# VIDEO.net
KiCad netlist of a schematic drawn in Altium Designer
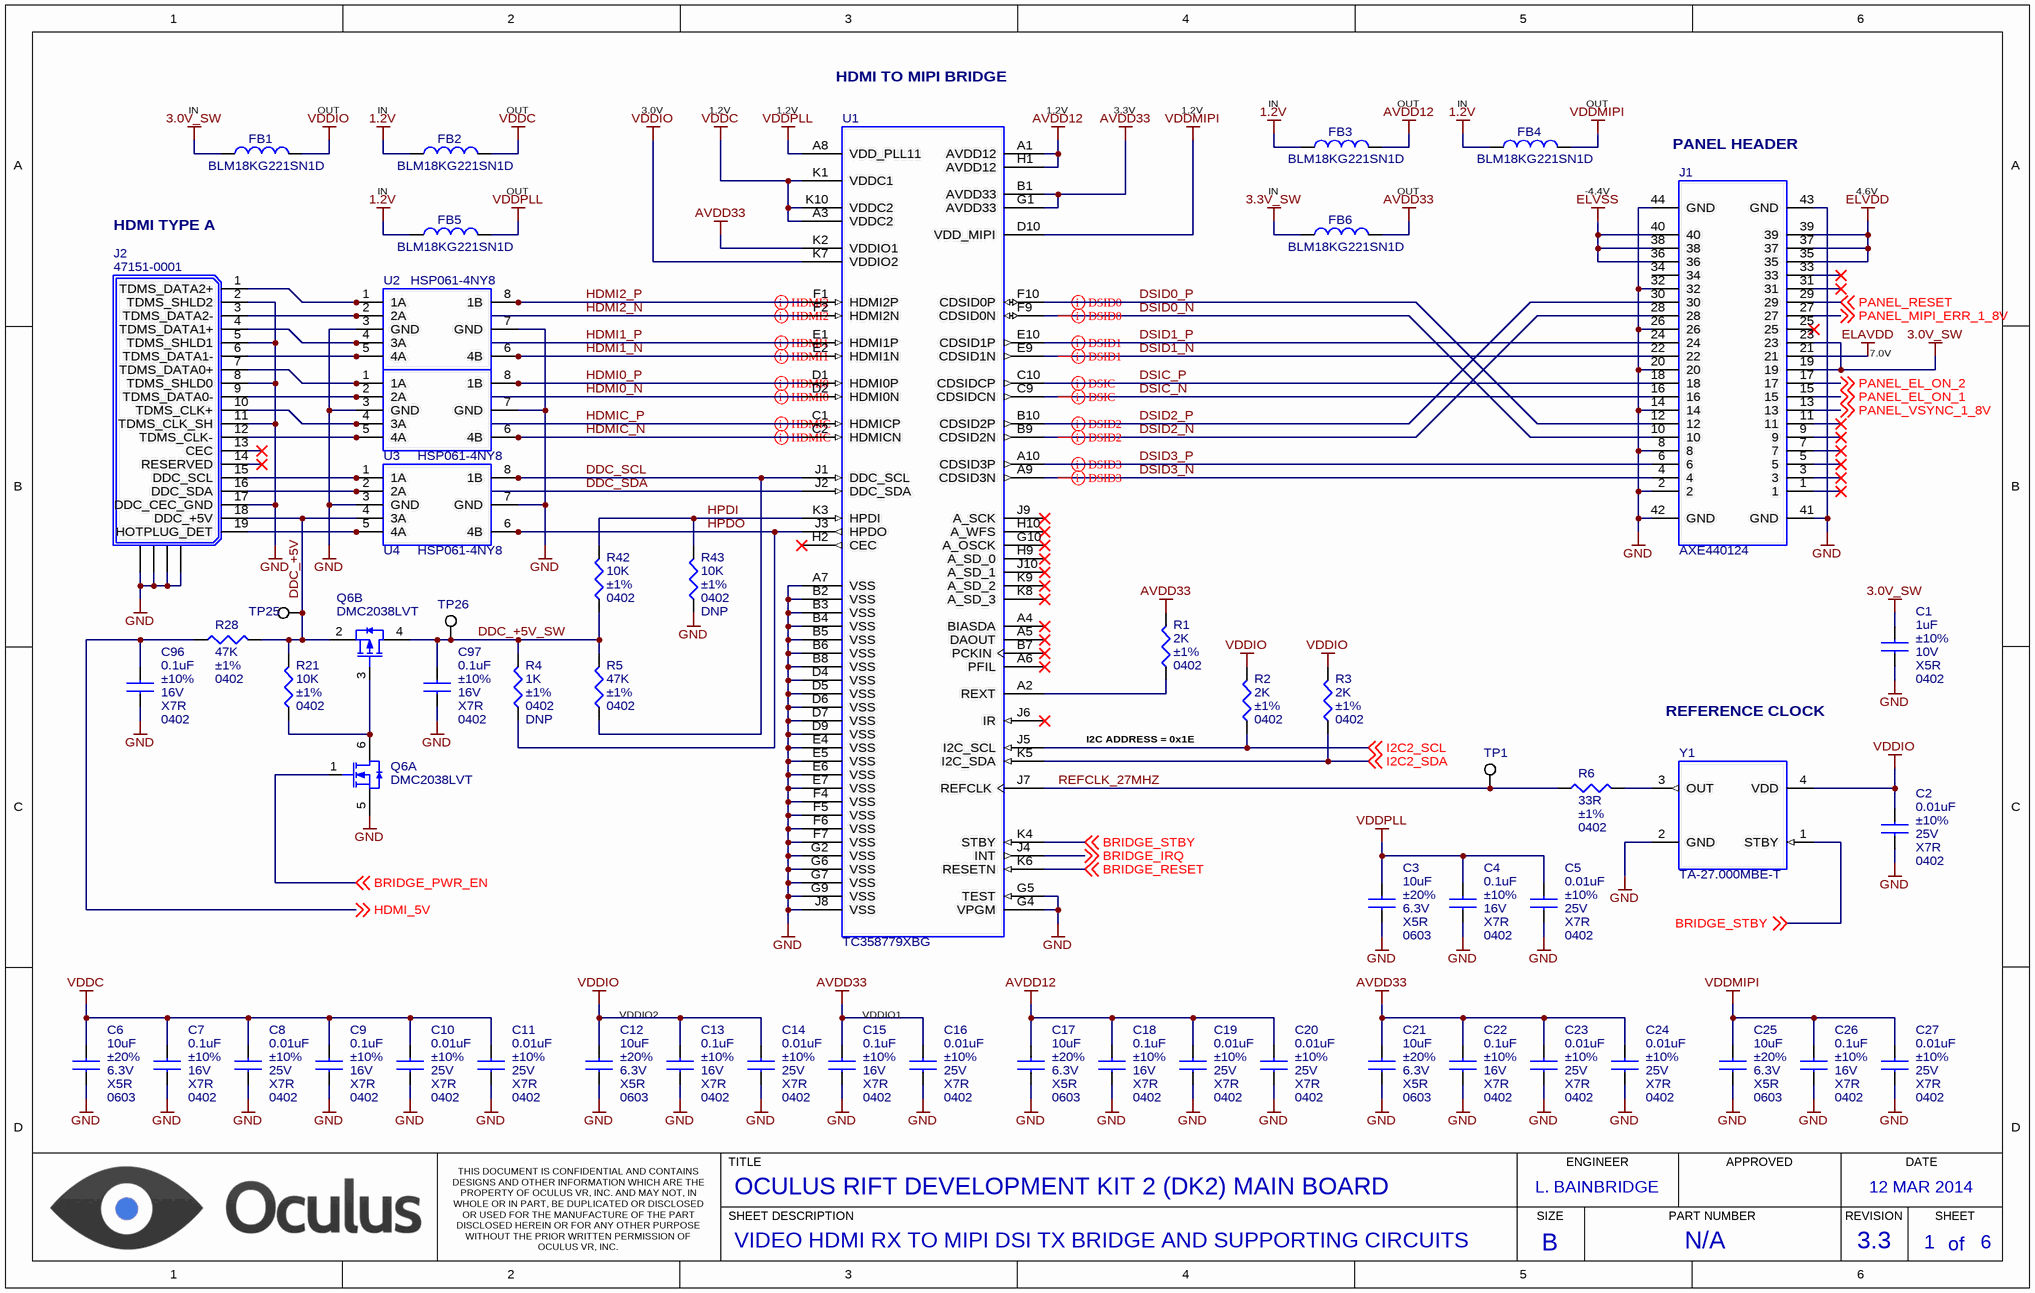
[diagram p0: VIDEO.SchDoc]

(export (version "E")
  (design (tool "Eeschema 10.0.6"))
  (components
    (comp (ref "C1")
      (value "1uF")
      (footprint "CAP_CERAMIC_0402")
      (description "CAP, CERAMIC, 1uF, ±10%, 10V, X5R, 0402")
      (fields
        (field (name "MANUFACTURER") "MURATA ELECTRONICS")
        (field (name "PART NUMBER") "GRM155R61A105KE15D")
        (field (name "TOLERANCE") "±10%")
        (field (name "VOLTAGE") "10V")
        (field (name "DIELECTRIC") "X5R")
        (field (name "PACKAGE") "0402")
      )
      (libsource (lib "DK2") (part "CAP, CERAMIC"))
    )
    (comp (ref "C2")
      (value "0.01uF")
      (footprint "CAP_CERAMIC_0402")
      (description "CAP, CERAMIC, 0.01uF, ±10%, 25V, X7R, 0402")
      (fields
        (field (name "MANUFACTURER") "MURATA ELECTRONICS")
        (field (name "PART NUMBER") "GRM155R71E103KA01D")
        (field (name "TOLERANCE") "±10%")
        (field (name "VOLTAGE") "25V")
        (field (name "DIELECTRIC") "X7R")
        (field (name "PACKAGE") "0402")
      )
      (libsource (lib "DK2") (part "CAP, CERAMIC"))
    )
    (comp (ref "C3")
      (value "10uF")
      (footprint "CAP_CERAMIC_0603")
      (description "CAP, CERAMIC, 10uF, ±20%, 6.3V, X5R, 0603")
      (fields
        (field (name "MANUFACTURER") "MURATA ELECTRONICS")
        (field (name "PART NUMBER") "GRM188R60J106ME47D")
        (field (name "TOLERANCE") "±20%")
        (field (name "VOLTAGE") "6.3V")
        (field (name "DIELECTRIC") "X5R")
        (field (name "PACKAGE") "0603")
      )
      (libsource (lib "DK2") (part "CAP, CERAMIC"))
    )
    (comp (ref "C4")
      (value "0.1uF")
      (footprint "CAP_CERAMIC_0402")
      (description "CAP, CERAMIC, 0.1uF, ±10%, 16V, X7R, 0402")
      (fields
        (field (name "MANUFACTURER") "MURATA ELECTRONICS")
        (field (name "PART NUMBER") "GRM155R71C104KA88D")
        (field (name "TOLERANCE") "±10%")
        (field (name "VOLTAGE") "16V")
        (field (name "DIELECTRIC") "X7R")
        (field (name "PACKAGE") "0402")
      )
      (libsource (lib "DK2") (part "CAP, CERAMIC"))
    )
    (comp (ref "C5")
      (value "0.01uF")
      (footprint "CAP_CERAMIC_0402")
      (description "CAP, CERAMIC, 0.01uF, ±10%, 25V, X7R, 0402")
      (fields
        (field (name "MANUFACTURER") "MURATA ELECTRONICS")
        (field (name "PART NUMBER") "GRM155R71E103KA01D")
        (field (name "TOLERANCE") "±10%")
        (field (name "VOLTAGE") "25V")
        (field (name "DIELECTRIC") "X7R")
        (field (name "PACKAGE") "0402")
      )
      (libsource (lib "DK2") (part "CAP, CERAMIC"))
    )
    (comp (ref "C6")
      (value "10uF")
      (footprint "CAP_CERAMIC_0603")
      (description "CAP, CERAMIC, 10uF, ±20%, 6.3V, X5R, 0603")
      (fields
        (field (name "MANUFACTURER") "MURATA ELECTRONICS")
        (field (name "PART NUMBER") "GRM188R60J106ME47D")
        (field (name "TOLERANCE") "±20%")
        (field (name "VOLTAGE") "6.3V")
        (field (name "DIELECTRIC") "X5R")
        (field (name "PACKAGE") "0603")
      )
      (libsource (lib "DK2") (part "CAP, CERAMIC"))
    )
    (comp (ref "C7")
      (value "0.1uF")
      (footprint "CAP_CERAMIC_0402")
      (description "CAP, CERAMIC, 0.1uF, ±10%, 16V, X7R, 0402")
      (fields
        (field (name "MANUFACTURER") "MURATA ELECTRONICS")
        (field (name "PART NUMBER") "GRM155R71C104KA88D")
        (field (name "TOLERANCE") "±10%")
        (field (name "VOLTAGE") "16V")
        (field (name "DIELECTRIC") "X7R")
        (field (name "PACKAGE") "0402")
      )
      (libsource (lib "DK2") (part "CAP, CERAMIC"))
    )
    (comp (ref "C8")
      (value "0.01uF")
      (footprint "CAP_CERAMIC_0402")
      (description "CAP, CERAMIC, 0.01uF, ±10%, 25V, X7R, 0402")
      (fields
        (field (name "MANUFACTURER") "MURATA ELECTRONICS")
        (field (name "PART NUMBER") "GRM155R71E103KA01D")
        (field (name "TOLERANCE") "±10%")
        (field (name "VOLTAGE") "25V")
        (field (name "DIELECTRIC") "X7R")
        (field (name "PACKAGE") "0402")
      )
      (libsource (lib "DK2") (part "CAP, CERAMIC"))
    )
    (comp (ref "C9")
      (value "0.1uF")
      (footprint "CAP_CERAMIC_0402")
      (description "CAP, CERAMIC, 0.1uF, ±10%, 16V, X7R, 0402")
      (fields
        (field (name "MANUFACTURER") "MURATA ELECTRONICS")
        (field (name "PART NUMBER") "GRM155R71C104KA88D")
        (field (name "TOLERANCE") "±10%")
        (field (name "VOLTAGE") "16V")
        (field (name "DIELECTRIC") "X7R")
        (field (name "PACKAGE") "0402")
      )
      (libsource (lib "DK2") (part "CAP, CERAMIC"))
    )
    (comp (ref "C10")
      (value "0.01uF")
      (footprint "CAP_CERAMIC_0402")
      (description "CAP, CERAMIC, 0.01uF, ±10%, 25V, X7R, 0402")
      (fields
        (field (name "MANUFACTURER") "MURATA ELECTRONICS")
        (field (name "PART NUMBER") "GRM155R71E103KA01D")
        (field (name "TOLERANCE") "±10%")
        (field (name "VOLTAGE") "25V")
        (field (name "DIELECTRIC") "X7R")
        (field (name "PACKAGE") "0402")
      )
      (libsource (lib "DK2") (part "CAP, CERAMIC"))
    )
    (comp (ref "C11")
      (value "0.01uF")
      (footprint "CAP_CERAMIC_0402")
      (description "CAP, CERAMIC, 0.01uF, ±10%, 25V, X7R, 0402")
      (fields
        (field (name "MANUFACTURER") "MURATA ELECTRONICS")
        (field (name "PART NUMBER") "GRM155R71E103KA01D")
        (field (name "TOLERANCE") "±10%")
        (field (name "VOLTAGE") "25V")
        (field (name "DIELECTRIC") "X7R")
        (field (name "PACKAGE") "0402")
      )
      (libsource (lib "DK2") (part "CAP, CERAMIC"))
    )
    (comp (ref "C12")
      (value "10uF")
      (footprint "CAP_CERAMIC_0603")
      (description "CAP, CERAMIC, 10uF, ±20%, 6.3V, X5R, 0603")
      (fields
        (field (name "MANUFACTURER") "MURATA ELECTRONICS")
        (field (name "PART NUMBER") "GRM188R60J106ME47D")
        (field (name "TOLERANCE") "±20%")
        (field (name "VOLTAGE") "6.3V")
        (field (name "DIELECTRIC") "X5R")
        (field (name "PACKAGE") "0603")
      )
      (libsource (lib "DK2") (part "CAP, CERAMIC"))
    )
    (comp (ref "C13")
      (value "0.1uF")
      (footprint "CAP_CERAMIC_0402")
      (description "CAP, CERAMIC, 0.1uF, ±10%, 16V, X7R, 0402")
      (fields
        (field (name "MANUFACTURER") "MURATA ELECTRONICS")
        (field (name "PART NUMBER") "GRM155R71C104KA88D")
        (field (name "TOLERANCE") "±10%")
        (field (name "VOLTAGE") "16V")
        (field (name "DIELECTRIC") "X7R")
        (field (name "PACKAGE") "0402")
      )
      (libsource (lib "DK2") (part "CAP, CERAMIC"))
    )
    (comp (ref "C14")
      (value "0.01uF")
      (footprint "CAP_CERAMIC_0402")
      (description "CAP, CERAMIC, 0.01uF, ±10%, 25V, X7R, 0402")
      (fields
        (field (name "MANUFACTURER") "MURATA ELECTRONICS")
        (field (name "PART NUMBER") "GRM155R71E103KA01D")
        (field (name "TOLERANCE") "±10%")
        (field (name "VOLTAGE") "25V")
        (field (name "DIELECTRIC") "X7R")
        (field (name "PACKAGE") "0402")
      )
      (libsource (lib "DK2") (part "CAP, CERAMIC"))
    )
    (comp (ref "C15")
      (value "0.1uF")
      (footprint "CAP_CERAMIC_0402")
      (description "CAP, CERAMIC, 0.1uF, ±10%, 16V, X7R, 0402")
      (fields
        (field (name "MANUFACTURER") "MURATA ELECTRONICS")
        (field (name "PART NUMBER") "GRM155R71C104KA88D")
        (field (name "TOLERANCE") "±10%")
        (field (name "VOLTAGE") "16V")
        (field (name "DIELECTRIC") "X7R")
        (field (name "PACKAGE") "0402")
      )
      (libsource (lib "DK2") (part "CAP, CERAMIC"))
    )
    (comp (ref "C16")
      (value "0.01uF")
      (footprint "CAP_CERAMIC_0402")
      (description "CAP, CERAMIC, 0.01uF, ±10%, 25V, X7R, 0402")
      (fields
        (field (name "MANUFACTURER") "MURATA ELECTRONICS")
        (field (name "PART NUMBER") "GRM155R71E103KA01D")
        (field (name "TOLERANCE") "±10%")
        (field (name "VOLTAGE") "25V")
        (field (name "DIELECTRIC") "X7R")
        (field (name "PACKAGE") "0402")
      )
      (libsource (lib "DK2") (part "CAP, CERAMIC"))
    )
    (comp (ref "C17")
      (value "10uF")
      (footprint "CAP_CERAMIC_0603")
      (description "CAP, CERAMIC, 10uF, ±20%, 6.3V, X5R, 0603")
      (fields
        (field (name "MANUFACTURER") "MURATA ELECTRONICS")
        (field (name "PART NUMBER") "GRM188R60J106ME47D")
        (field (name "TOLERANCE") "±20%")
        (field (name "VOLTAGE") "6.3V")
        (field (name "DIELECTRIC") "X5R")
        (field (name "PACKAGE") "0603")
      )
      (libsource (lib "DK2") (part "CAP, CERAMIC"))
    )
    (comp (ref "C18")
      (value "0.1uF")
      (footprint "CAP_CERAMIC_0402")
      (description "CAP, CERAMIC, 0.1uF, ±10%, 16V, X7R, 0402")
      (fields
        (field (name "MANUFACTURER") "MURATA ELECTRONICS")
        (field (name "PART NUMBER") "GRM155R71C104KA88D")
        (field (name "TOLERANCE") "±10%")
        (field (name "VOLTAGE") "16V")
        (field (name "DIELECTRIC") "X7R")
        (field (name "PACKAGE") "0402")
      )
      (libsource (lib "DK2") (part "CAP, CERAMIC"))
    )
    (comp (ref "C19")
      (value "0.01uF")
      (footprint "CAP_CERAMIC_0402")
      (description "CAP, CERAMIC, 0.01uF, ±10%, 25V, X7R, 0402")
      (fields
        (field (name "MANUFACTURER") "MURATA ELECTRONICS")
        (field (name "PART NUMBER") "GRM155R71E103KA01D")
        (field (name "TOLERANCE") "±10%")
        (field (name "VOLTAGE") "25V")
        (field (name "DIELECTRIC") "X7R")
        (field (name "PACKAGE") "0402")
      )
      (libsource (lib "DK2") (part "CAP, CERAMIC"))
    )
    (comp (ref "C20")
      (value "0.01uF")
      (footprint "CAP_CERAMIC_0402")
      (description "CAP, CERAMIC, 0.01uF, ±10%, 25V, X7R, 0402")
      (fields
        (field (name "MANUFACTURER") "MURATA ELECTRONICS")
        (field (name "PART NUMBER") "GRM155R71E103KA01D")
        (field (name "TOLERANCE") "±10%")
        (field (name "VOLTAGE") "25V")
        (field (name "DIELECTRIC") "X7R")
        (field (name "PACKAGE") "0402")
      )
      (libsource (lib "DK2") (part "CAP, CERAMIC"))
    )
    (comp (ref "C21")
      (value "10uF")
      (footprint "CAP_CERAMIC_0603")
      (description "CAP, CERAMIC, 10uF, ±20%, 6.3V, X5R, 0603")
      (fields
        (field (name "MANUFACTURER") "MURATA ELECTRONICS")
        (field (name "PART NUMBER") "GRM188R60J106ME47D")
        (field (name "TOLERANCE") "±20%")
        (field (name "VOLTAGE") "6.3V")
        (field (name "DIELECTRIC") "X5R")
        (field (name "PACKAGE") "0603")
      )
      (libsource (lib "DK2") (part "CAP, CERAMIC"))
    )
    (comp (ref "C22")
      (value "0.1uF")
      (footprint "CAP_CERAMIC_0402")
      (description "CAP, CERAMIC, 0.1uF, ±10%, 16V, X7R, 0402")
      (fields
        (field (name "MANUFACTURER") "MURATA ELECTRONICS")
        (field (name "PART NUMBER") "GRM155R71C104KA88D")
        (field (name "TOLERANCE") "±10%")
        (field (name "VOLTAGE") "16V")
        (field (name "DIELECTRIC") "X7R")
        (field (name "PACKAGE") "0402")
      )
      (libsource (lib "DK2") (part "CAP, CERAMIC"))
    )
    (comp (ref "C23")
      (value "0.01uF")
      (footprint "CAP_CERAMIC_0402")
      (description "CAP, CERAMIC, 0.01uF, ±10%, 25V, X7R, 0402")
      (fields
        (field (name "MANUFACTURER") "MURATA ELECTRONICS")
        (field (name "PART NUMBER") "GRM155R71E103KA01D")
        (field (name "TOLERANCE") "±10%")
        (field (name "VOLTAGE") "25V")
        (field (name "DIELECTRIC") "X7R")
        (field (name "PACKAGE") "0402")
      )
      (libsource (lib "DK2") (part "CAP, CERAMIC"))
    )
    (comp (ref "C24")
      (value "0.01uF")
      (footprint "CAP_CERAMIC_0402")
      (description "CAP, CERAMIC, 0.01uF, ±10%, 25V, X7R, 0402")
      (fields
        (field (name "MANUFACTURER") "MURATA ELECTRONICS")
        (field (name "PART NUMBER") "GRM155R71E103KA01D")
        (field (name "TOLERANCE") "±10%")
        (field (name "VOLTAGE") "25V")
        (field (name "DIELECTRIC") "X7R")
        (field (name "PACKAGE") "0402")
      )
      (libsource (lib "DK2") (part "CAP, CERAMIC"))
    )
    (comp (ref "C25")
      (value "10uF")
      (footprint "CAP_CERAMIC_0603")
      (description "CAP, CERAMIC, 10uF, ±20%, 6.3V, X5R, 0603")
      (fields
        (field (name "MANUFACTURER") "MURATA ELECTRONICS")
        (field (name "PART NUMBER") "GRM188R60J106ME47D")
        (field (name "TOLERANCE") "±20%")
        (field (name "VOLTAGE") "6.3V")
        (field (name "DIELECTRIC") "X5R")
        (field (name "PACKAGE") "0603")
      )
      (libsource (lib "DK2") (part "CAP, CERAMIC"))
    )
    (comp (ref "C26")
      (value "0.1uF")
      (footprint "CAP_CERAMIC_0402")
      (description "CAP, CERAMIC, 0.1uF, ±10%, 16V, X7R, 0402")
      (fields
        (field (name "MANUFACTURER") "MURATA ELECTRONICS")
        (field (name "PART NUMBER") "GRM155R71C104KA88D")
        (field (name "TOLERANCE") "±10%")
        (field (name "VOLTAGE") "16V")
        (field (name "DIELECTRIC") "X7R")
        (field (name "PACKAGE") "0402")
      )
      (libsource (lib "DK2") (part "CAP, CERAMIC"))
    )
    (comp (ref "C27")
      (value "0.01uF")
      (footprint "CAP_CERAMIC_0402")
      (description "CAP, CERAMIC, 0.01uF, ±10%, 25V, X7R, 0402")
      (fields
        (field (name "MANUFACTURER") "MURATA ELECTRONICS")
        (field (name "PART NUMBER") "GRM155R71E103KA01D")
        (field (name "TOLERANCE") "±10%")
        (field (name "VOLTAGE") "25V")
        (field (name "DIELECTRIC") "X7R")
        (field (name "PACKAGE") "0402")
      )
      (libsource (lib "DK2") (part "CAP, CERAMIC"))
    )
    (comp (ref "C96")
      (value "0.1uF")
      (footprint "CAP_CERAMIC_0402")
      (description "CAP, CERAMIC, 0.1uF, ±10%, 16V, X7R, 0402")
      (fields
        (field (name "MANUFACTURER") "MURATA ELECTRONICS")
        (field (name "PART NUMBER") "GRM155R71C104KA88D")
        (field (name "TOLERANCE") "±10%")
        (field (name "VOLTAGE") "16V")
        (field (name "DIELECTRIC") "X7R")
        (field (name "PACKAGE") "0402")
      )
      (libsource (lib "DK2") (part "CAP, CERAMIC"))
    )
    (comp (ref "C97")
      (value "0.1uF")
      (footprint "CAP_CERAMIC_0402")
      (description "CAP, CERAMIC, 0.1uF, ±10%, 16V, X7R, 0402")
      (fields
        (field (name "MANUFACTURER") "MURATA ELECTRONICS")
        (field (name "PART NUMBER") "GRM155R71C104KA88D")
        (field (name "TOLERANCE") "±10%")
        (field (name "VOLTAGE") "16V")
        (field (name "DIELECTRIC") "X7R")
        (field (name "PACKAGE") "0402")
      )
      (libsource (lib "DK2") (part "CAP, CERAMIC"))
    )
    (comp (ref "FB1")
      (value "BLM18KG221SN1D")
      (footprint "INDUCTOR_0603")
      (description "FERRITE CHIP BEAD, 220 OHM @ 100MHz, 2.2A, 0603")
      (fields (field (name "MANUFACTURER") "MURATA ELECTRONICS"))
      (libsource (lib "DK2") (part "INDUCTOR"))
    )
    (comp (ref "FB2")
      (value "BLM18KG221SN1D")
      (footprint "INDUCTOR_0603")
      (description "FERRITE CHIP BEAD, 220 OHM @ 100MHz, 2.2A, 0603")
      (fields (field (name "MANUFACTURER") "MURATA ELECTRONICS"))
      (libsource (lib "DK2") (part "INDUCTOR"))
    )
    (comp (ref "FB3")
      (value "BLM18KG221SN1D")
      (footprint "INDUCTOR_0603")
      (description "FERRITE CHIP BEAD, 220 OHM @ 100MHz, 2.2A, 0603")
      (fields (field (name "MANUFACTURER") "MURATA ELECTRONICS"))
      (libsource (lib "DK2") (part "INDUCTOR"))
    )
    (comp (ref "FB4")
      (value "BLM18KG221SN1D")
      (footprint "INDUCTOR_0603")
      (description "FERRITE CHIP BEAD, 220 OHM @ 100MHz, 2.2A, 0603")
      (fields (field (name "MANUFACTURER") "MURATA ELECTRONICS"))
      (libsource (lib "DK2") (part "INDUCTOR"))
    )
    (comp (ref "FB5")
      (value "BLM18KG221SN1D")
      (footprint "INDUCTOR_0603")
      (description "FERRITE CHIP BEAD, 220 OHM @ 100MHz, 2.2A, 0603")
      (fields (field (name "MANUFACTURER") "MURATA ELECTRONICS"))
      (libsource (lib "DK2") (part "INDUCTOR"))
    )
    (comp (ref "FB6")
      (value "BLM18KG221SN1D")
      (footprint "INDUCTOR_0603")
      (description "FERRITE CHIP BEAD, 220 OHM @ 100MHz, 2.2A, 0603")
      (fields (field (name "MANUFACTURER") "MURATA ELECTRONICS"))
      (libsource (lib "DK2") (part "INDUCTOR"))
    )
    (comp (ref "J1")
      (value "AXE440124")
      (footprint "AXE440124")
      (description "CONNECTOR, 40-PIN HEADER, 0.4MM PITCH")
      (fields (field (name "MANUFACTURER") "PANASONIC"))
      (libsource (lib "DK2") (part "AXE440124"))
    )
    (comp (ref "J2")
      (value "47151-0001")
      (footprint "47151-0001")
      (description "CONNECTOR, HDMI TYPE A, R/A, SMD")
      (fields (field (name "MANUFACTURER") "MOLEX"))
      (libsource (lib "DK2") (part "47151-0001"))
    )
    (comp (ref "Q6")
      (value "DMC2038LVT")
      (footprint "TSOT26")
      (description "FET, COMPLEMENTARY, LOGIC LEVEL")
      (fields (field (name "MANUFACTURER") "DIODES INC"))
      (libsource (lib "DK2") (part "DMC2038LVT"))
    )
    (comp (ref "R1")
      (value "2K")
      (footprint "RESISTOR_0402")
      (description "RES, 2K OHM, 1/10W, ±1%, 0402")
      (fields
        (field (name "MANUFACTURER") "PANASONIC")
        (field (name "PART NUMBER") "ERJ-2RKF2001X")
        (field (name "PACKAGE") "0402")
        (field (name "TOLERANCE") "±1%")
      )
      (libsource (lib "DK2") (part "RESISTOR"))
    )
    (comp (ref "R2")
      (value "2K")
      (footprint "RESISTOR_0402")
      (description "RES, 2K OHM, 1/10W, ±1%, 0402")
      (fields
        (field (name "MANUFACTURER") "PANASONIC")
        (field (name "PART NUMBER") "ERJ-2RKF2001X")
        (field (name "PACKAGE") "0402")
        (field (name "TOLERANCE") "±1%")
      )
      (libsource (lib "DK2") (part "RESISTOR"))
    )
    (comp (ref "R3")
      (value "2K")
      (footprint "RESISTOR_0402")
      (description "RES, 2K OHM, 1/10W, ±1%, 0402")
      (fields
        (field (name "MANUFACTURER") "PANASONIC")
        (field (name "PART NUMBER") "ERJ-2RKF2001X")
        (field (name "PACKAGE") "0402")
        (field (name "TOLERANCE") "±1%")
      )
      (libsource (lib "DK2") (part "RESISTOR"))
    )
    (comp (ref "R4")
      (value "1K")
      (footprint "RESISTOR_0402")
      (description "RES, 1K OHM, 1/10W, ±1%, 0402")
      (fields
        (field (name "MANUFACTURER") "PANASONIC")
        (field (name "PART NUMBER") "ERJ-2RKF1001X")
        (field (name "PACKAGE") "0402")
        (field (name "TOLERANCE") "±1%")
        (field (name "DNP") "DNP")
      )
      (libsource (lib "DK2") (part "RESISTOR"))
    )
    (comp (ref "R5")
      (value "47K")
      (footprint "RESISTOR_0402")
      (description "RES, 47K OHM, 1/10W, ±1%, 0402")
      (fields
        (field (name "MANUFACTURER") "PANASONIC")
        (field (name "PART NUMBER") "ERJ-2RKF4702X")
        (field (name "PACKAGE") "0402")
        (field (name "TOLERANCE") "±1%")
      )
      (libsource (lib "DK2") (part "RESISTOR"))
    )
    (comp (ref "R6")
      (value "33R")
      (footprint "RESISTOR_0402")
      (description "RES, 33 OHM, 1/10W, ±1%, 0402")
      (fields
        (field (name "MANUFACTURER") "PANASONIC")
        (field (name "PART NUMBER") "ERJ-2RKF33R0X")
        (field (name "PACKAGE") "0402")
        (field (name "TOLERANCE") "±1%")
      )
      (libsource (lib "DK2") (part "RESISTOR"))
    )
    (comp (ref "R21")
      (value "10K")
      (footprint "RESISTOR_0402")
      (description "RES, 10K OHM, 1/10W, ±1%, 0402")
      (fields
        (field (name "MANUFACTURER") "PANASONIC")
        (field (name "PART NUMBER") "ERJ-2RKF1002X")
        (field (name "PACKAGE") "0402")
        (field (name "TOLERANCE") "±1%")
      )
      (libsource (lib "DK2") (part "RESISTOR"))
    )
    (comp (ref "R28")
      (value "47K")
      (footprint "RESISTOR_0402")
      (description "RES, 47K OHM, 1/10W, ±1%, 0402")
      (fields
        (field (name "MANUFACTURER") "PANASONIC")
        (field (name "PART NUMBER") "ERJ-2RKF4702X")
        (field (name "PACKAGE") "0402")
        (field (name "TOLERANCE") "±1%")
      )
      (libsource (lib "DK2") (part "RESISTOR"))
    )
    (comp (ref "R42")
      (value "10K")
      (footprint "RESISTOR_0402")
      (description "RES, 10K OHM, 1/10W, ±1%, 0402")
      (fields
        (field (name "MANUFACTURER") "PANASONIC")
        (field (name "PART NUMBER") "ERJ-2RKF1002X")
        (field (name "PACKAGE") "0402")
        (field (name "TOLERANCE") "±1%")
      )
      (libsource (lib "DK2") (part "RESISTOR"))
    )
    (comp (ref "R43")
      (value "10K")
      (footprint "RESISTOR_0402")
      (description "RES, 10K OHM, 1/10W, ±1%, 0402")
      (fields
        (field (name "MANUFACTURER") "PANASONIC")
        (field (name "PART NUMBER") "ERJ-2RKF1002X")
        (field (name "PACKAGE") "0402")
        (field (name "TOLERANCE") "±1%")
        (field (name "DNP") "DNP")
      )
      (libsource (lib "DK2") (part "RESISTOR"))
    )
    (comp (ref "TP1")
      (value "TEST POINT")
      (footprint "TEST_POINT_PAD_1MM")
      (libsource (lib "DK2") (part "TEST_POINT_GENERIC"))
    )
    (comp (ref "TP25")
      (value "TEST POINT")
      (footprint "TEST_POINT_PAD_1MM")
      (libsource (lib "DK2") (part "TEST_POINT_GENERIC"))
    )
    (comp (ref "TP26")
      (value "TEST POINT")
      (footprint "TEST_POINT_PAD_1MM")
      (libsource (lib "DK2") (part "TEST_POINT_GENERIC"))
    )
    (comp (ref "U1")
      (value "TC358779XBG")
      (footprint "BGA80")
      (description "IC, HDMI RX TO MIPI DSI TX BRIDGE")
      (fields (field (name "MANUFACTURER") "TOSHIBA"))
      (libsource (lib "DK2") (part "TC358779XBG"))
    )
    (comp (ref "U2")
      (value "HSP061-4NY8")
      (footprint "HSP061-4NY8")
      (description "IC, 4-LINE ESD PROTECTION ARRAY, HIGH SPEED")
      (fields (field (name "MANUFACTURER") "STMICROELECTRONICS"))
      (libsource (lib "DK2") (part "HSP061-4NY8"))
    )
    (comp (ref "U3")
      (value "HSP061-4NY8")
      (footprint "HSP061-4NY8")
      (description "IC, 4-LINE ESD PROTECTION ARRAY, HIGH SPEED")
      (fields (field (name "MANUFACTURER") "STMICROELECTRONICS"))
      (libsource (lib "DK2") (part "HSP061-4NY8"))
    )
    (comp (ref "U4")
      (value "HSP061-4NY8")
      (footprint "HSP061-4NY8")
      (description "IC, 4-LINE ESD PROTECTION ARRAY, HIGH SPEED")
      (fields (field (name "MANUFACTURER") "STMICROELECTRONICS"))
      (libsource (lib "DK2") (part "HSP061-4NY8"))
    )
    (comp (ref "Y1")
      (value "TA-27.000MBE-T")
      (footprint "TXC_TD")
      (description "OSCILLATOR, 27MHz, MEMS, 3.3V, 50PPM")
      (fields (field (name "MANUFACTURER") "TXC"))
      (libsource (lib "DK2") (part "TA-27.000MBE-T"))
    )
  )
  (nets
    (net (code "1") (name "/DDC_+5V") (class "Default")
      (node (ref "J2") (pin "18") (pinfunction "DDC_+5V_18") (pintype "passive"))
      (node (ref "Q6") (pin "2") (pinfunction "S_2") (pintype "passive"))
      (node (ref "R21") (pin "2") (pinfunction "2_2") (pintype "passive"))
      (node (ref "R28") (pin "2") (pinfunction "2_2") (pintype "passive"))
      (node (ref "TP25") (pin "1") (pinfunction "1_1") (pintype "passive"))
      (node (ref "U4") (pin "4") (pinfunction "3A_4") (pintype "passive"))
    )
    (net (code "2") (name "/DDC_+5V_SW") (class "Default")
      (node (ref "C97") (pin "1") (pinfunction "1_1") (pintype "passive"))
      (node (ref "Q6") (pin "4") (pinfunction "D_4") (pintype "passive"))
      (node (ref "R4") (pin "2") (pinfunction "2_2") (pintype "passive"))
      (node (ref "R42") (pin "1") (pinfunction "1_1") (pintype "passive"))
      (node (ref "R5") (pin "2") (pinfunction "2_2") (pintype "passive"))
      (node (ref "TP26") (pin "1") (pinfunction "1_1") (pintype "passive"))
    )
    (net (code "3") (name "/DDC_SCL") (class "Default")
      (node (ref "J2") (pin "15") (pinfunction "DDC_SCL_15") (pintype "passive"))
      (node (ref "R5") (pin "1") (pinfunction "1_1") (pintype "passive"))
      (node (ref "U1") (pin "J1") (pinfunction "DDC_SCL_J1") (pintype "input"))
      (node (ref "U4") (pin "1") (pinfunction "1A_1") (pintype "passive"))
      (node (ref "U4") (pin "8") (pinfunction "1B_8") (pintype "passive"))
    )
    (net (code "4") (name "/DDC_SDA") (class "Default")
      (node (ref "J2") (pin "16") (pinfunction "DDC_SDA_16") (pintype "passive"))
      (node (ref "U1") (pin "J2") (pinfunction "DDC_SDA_J2") (pintype "input"))
      (node (ref "U4") (pin "2") (pinfunction "2A_2") (pintype "passive"))
    )
    (net (code "5") (name "/DSIC_N") (class "Default")
      (node (ref "J1") (pin "16") (pinfunction "16_16") (pintype "passive"))
      (node (ref "U1") (pin "C9") (pinfunction "CDSIDCN_C9") (pintype "output"))
    )
    (net (code "6") (name "/DSIC_P") (class "Default")
      (node (ref "J1") (pin "18") (pinfunction "18_18") (pintype "passive"))
      (node (ref "U1") (pin "C10") (pinfunction "CDSIDCP_C10") (pintype "output"))
    )
    (net (code "7") (name "/DSID0_N") (class "Default")
      (node (ref "J1") (pin "10") (pinfunction "10_10") (pintype "passive"))
      (node (ref "U1") (pin "F9") (pinfunction "CDSID0N_F9") (pintype "bidirectional"))
    )
    (net (code "8") (name "/DSID0_P") (class "Default")
      (node (ref "J1") (pin "12") (pinfunction "12_12") (pintype "passive"))
      (node (ref "U1") (pin "F10") (pinfunction "CDSID0P_F10") (pintype "bidirectional"))
    )
    (net (code "9") (name "/DSID1_N") (class "Default")
      (node (ref "J1") (pin "22") (pinfunction "22_22") (pintype "passive"))
      (node (ref "U1") (pin "E9") (pinfunction "CDSID1N_E9") (pintype "output"))
    )
    (net (code "10") (name "/DSID1_P") (class "Default")
      (node (ref "J1") (pin "24") (pinfunction "24_24") (pintype "passive"))
      (node (ref "U1") (pin "E10") (pinfunction "CDSID1P_E10") (pintype "output"))
    )
    (net (code "11") (name "/DSID2_N") (class "Default")
      (node (ref "J1") (pin "28") (pinfunction "28_28") (pintype "passive"))
      (node (ref "U1") (pin "B9") (pinfunction "CDSID2N_B9") (pintype "output"))
    )
    (net (code "12") (name "/DSID2_P") (class "Default")
      (node (ref "J1") (pin "30") (pinfunction "30_30") (pintype "passive"))
      (node (ref "U1") (pin "B10") (pinfunction "CDSID2P_B10") (pintype "output"))
    )
    (net (code "13") (name "/DSID3_N") (class "Default")
      (node (ref "J1") (pin "4") (pinfunction "4_4") (pintype "passive"))
      (node (ref "U1") (pin "A9") (pinfunction "CDSID3N_A9") (pintype "output"))
    )
    (net (code "14") (name "/DSID3_P") (class "Default")
      (node (ref "J1") (pin "6") (pinfunction "6_6") (pintype "passive"))
      (node (ref "U1") (pin "A10") (pinfunction "CDSID3P_A10") (pintype "output"))
    )
    (net (code "15") (name "/HDMI0_N") (class "Default")
      (node (ref "J2") (pin "9") (pinfunction "TDMS_DATA0-_9") (pintype "passive"))
      (node (ref "U1") (pin "D2") (pinfunction "HDMI0N_D2") (pintype "input"))
      (node (ref "U3") (pin "2") (pinfunction "2A_2") (pintype "passive"))
    )
    (net (code "16") (name "/HDMI0_P") (class "Default")
      (node (ref "J2") (pin "7") (pinfunction "TDMS_DATA0+_7") (pintype "passive"))
      (node (ref "U1") (pin "D1") (pinfunction "HDMI0P_D1") (pintype "input"))
      (node (ref "U3") (pin "1") (pinfunction "1A_1") (pintype "passive"))
      (node (ref "U3") (pin "8") (pinfunction "1B_8") (pintype "passive"))
    )
    (net (code "17") (name "/HDMI1_N") (class "Default")
      (node (ref "J2") (pin "6") (pinfunction "TDMS_DATA1-_6") (pintype "passive"))
      (node (ref "U1") (pin "E2") (pinfunction "HDMI1N_E2") (pintype "input"))
      (node (ref "U2") (pin "5") (pinfunction "4A_5") (pintype "passive"))
      (node (ref "U2") (pin "6") (pinfunction "4B_6") (pintype "passive"))
    )
    (net (code "18") (name "/HDMI1_P") (class "Default")
      (node (ref "J2") (pin "4") (pinfunction "TDMS_DATA1+_4") (pintype "passive"))
      (node (ref "U1") (pin "E1") (pinfunction "HDMI1P_E1") (pintype "input"))
      (node (ref "U2") (pin "4") (pinfunction "3A_4") (pintype "passive"))
    )
    (net (code "19") (name "/HDMI2_N") (class "Default")
      (node (ref "J2") (pin "3") (pinfunction "TDMS_DATA2-_3") (pintype "passive"))
      (node (ref "U1") (pin "F2") (pinfunction "HDMI2N_F2") (pintype "input"))
      (node (ref "U2") (pin "2") (pinfunction "2A_2") (pintype "passive"))
    )
    (net (code "20") (name "/HDMI2_P") (class "Default")
      (node (ref "J2") (pin "1") (pinfunction "TDMS_DATA2+_1") (pintype "passive"))
      (node (ref "U1") (pin "F1") (pinfunction "HDMI2P_F1") (pintype "input"))
      (node (ref "U2") (pin "1") (pinfunction "1A_1") (pintype "passive"))
      (node (ref "U2") (pin "8") (pinfunction "1B_8") (pintype "passive"))
    )
    (net (code "21") (name "/HDMIC_N") (class "Default")
      (node (ref "J2") (pin "12") (pinfunction "TDMS_CLK-_12") (pintype "passive"))
      (node (ref "U1") (pin "C2") (pinfunction "HDMICN_C2") (pintype "input"))
      (node (ref "U3") (pin "5") (pinfunction "4A_5") (pintype "passive"))
      (node (ref "U3") (pin "6") (pinfunction "4B_6") (pintype "passive"))
    )
    (net (code "22") (name "/HDMIC_P") (class "Default")
      (node (ref "J2") (pin "10") (pinfunction "TDMS_CLK+_10") (pintype "passive"))
      (node (ref "U1") (pin "C1") (pinfunction "HDMICP_C1") (pintype "input"))
      (node (ref "U3") (pin "4") (pinfunction "3A_4") (pintype "passive"))
    )
    (net (code "23") (name "/HPDI") (class "Default")
      (node (ref "R42") (pin "2") (pinfunction "2_2") (pintype "passive"))
      (node (ref "R43") (pin "2") (pinfunction "2_2") (pintype "passive"))
      (node (ref "U1") (pin "K3") (pinfunction "HPDI_K3") (pintype "input"))
    )
    (net (code "24") (name "/HPDO") (class "Default")
      (node (ref "J2") (pin "19") (pinfunction "HOTPLUG_DET_19") (pintype "passive"))
      (node (ref "R4") (pin "1") (pinfunction "1_1") (pintype "passive"))
      (node (ref "U1") (pin "J3") (pinfunction "HPDO_J3") (pintype "output"))
      (node (ref "U4") (pin "5") (pinfunction "4A_5") (pintype "passive"))
      (node (ref "U4") (pin "6") (pinfunction "4B_6") (pintype "passive"))
    )
    (net (code "25") (name "/REFCLK_27MHZ") (class "Default")
      (node (ref "R6") (pin "1") (pinfunction "1_1") (pintype "passive"))
      (node (ref "TP1") (pin "1") (pinfunction "1_1") (pintype "passive"))
      (node (ref "U1") (pin "J7") (pinfunction "REFCLK_J7") (pintype "passive"))
    )
    (net (code "26") (name "1.2V") (class "Default")
      (node (ref "FB2") (pin "1") (pinfunction "1_1") (pintype "passive"))
      (node (ref "FB3") (pin "1") (pinfunction "1_1") (pintype "passive"))
      (node (ref "FB4") (pin "1") (pinfunction "1_1") (pintype "passive"))
      (node (ref "FB5") (pin "1") (pinfunction "1_1") (pintype "passive"))
    )
    (net (code "27") (name "3.0V_SW") (class "Default")
      (node (ref "C1") (pin "1") (pinfunction "1_1") (pintype "passive"))
      (node (ref "FB1") (pin "1") (pinfunction "1_1") (pintype "passive"))
      (node (ref "J1") (pin "19") (pinfunction "19_19") (pintype "passive"))
      (node (ref "J1") (pin "23") (pinfunction "23_23") (pintype "passive"))
    )
    (net (code "28") (name "3.3V_SW") (class "Default")
      (node (ref "FB6") (pin "1") (pinfunction "1_1") (pintype "passive"))
    )
    (net (code "29") (name "AVDD12") (class "Default")
      (node (ref "C17") (pin "1") (pinfunction "1_1") (pintype "passive"))
      (node (ref "C18") (pin "1") (pinfunction "1_1") (pintype "passive"))
      (node (ref "C19") (pin "1") (pinfunction "1_1") (pintype "passive"))
      (node (ref "C20") (pin "1") (pinfunction "1_1") (pintype "passive"))
      (node (ref "FB3") (pin "2") (pinfunction "2_2") (pintype "passive"))
      (node (ref "U1") (pin "A1") (pinfunction "AVDD12_A1") (pintype "power_in"))
      (node (ref "U1") (pin "H1") (pinfunction "AVDD12_H1") (pintype "power_in"))
    )
    (net (code "30") (name "AVDD33") (class "Default")
      (node (ref "C15") (pin "1") (pinfunction "1_1") (pintype "passive"))
      (node (ref "C16") (pin "1") (pinfunction "1_1") (pintype "passive"))
      (node (ref "C21") (pin "1") (pinfunction "1_1") (pintype "passive"))
      (node (ref "C22") (pin "1") (pinfunction "1_1") (pintype "passive"))
      (node (ref "C23") (pin "1") (pinfunction "1_1") (pintype "passive"))
      (node (ref "C24") (pin "1") (pinfunction "1_1") (pintype "passive"))
      (node (ref "FB6") (pin "2") (pinfunction "2_2") (pintype "passive"))
      (node (ref "R1") (pin "2") (pinfunction "2_2") (pintype "passive"))
      (node (ref "U1") (pin "B1") (pinfunction "AVDD33_B1") (pintype "power_in"))
      (node (ref "U1") (pin "G1") (pinfunction "AVDD33_G1") (pintype "power_in"))
      (node (ref "U1") (pin "K2") (pinfunction "VDDIO1_K2") (pintype "power_in"))
    )
    (net (code "31") (name "BRIDGE_IRQ") (class "Default")
      (node (ref "U1") (pin "J4") (pinfunction "INT_J4") (pintype "output"))
    )
    (net (code "32") (name "BRIDGE_PWR_EN") (class "Default")
      (node (ref "Q6") (pin "1") (pinfunction "G_1") (pintype "passive"))
    )
    (net (code "33") (name "BRIDGE_RESET") (class "Default")
      (node (ref "U1") (pin "K6") (pinfunction "RESETN_K6") (pintype "input"))
    )
    (net (code "34") (name "BRIDGE_STBY") (class "Default")
      (node (ref "U1") (pin "K4") (pinfunction "STBY_K4") (pintype "input"))
      (node (ref "Y1") (pin "1") (pinfunction "STBY_1") (pintype "input"))
    )
    (net (code "35") (name "ELAVDD") (class "Default")
      (node (ref "J1") (pin "21") (pinfunction "21_21") (pintype "passive"))
    )
    (net (code "36") (name "ELVDD") (class "Default")
      (node (ref "J1") (pin "35") (pinfunction "35_35") (pintype "passive"))
      (node (ref "J1") (pin "37") (pinfunction "37_37") (pintype "passive"))
      (node (ref "J1") (pin "39") (pinfunction "39_39") (pintype "passive"))
    )
    (net (code "37") (name "ELVSS") (class "Default")
      (node (ref "J1") (pin "36") (pinfunction "36_36") (pintype "passive"))
      (node (ref "J1") (pin "38") (pinfunction "38_38") (pintype "passive"))
      (node (ref "J1") (pin "40") (pinfunction "40_40") (pintype "passive"))
    )
    (net (code "38") (name "GND") (class "Default")
      (node (ref "C1") (pin "2") (pinfunction "2_2") (pintype "passive"))
      (node (ref "C10") (pin "2") (pinfunction "2_2") (pintype "passive"))
      (node (ref "C11") (pin "2") (pinfunction "2_2") (pintype "passive"))
      (node (ref "C12") (pin "2") (pinfunction "2_2") (pintype "passive"))
      (node (ref "C13") (pin "2") (pinfunction "2_2") (pintype "passive"))
      (node (ref "C14") (pin "2") (pinfunction "2_2") (pintype "passive"))
      (node (ref "C15") (pin "2") (pinfunction "2_2") (pintype "passive"))
      (node (ref "C16") (pin "2") (pinfunction "2_2") (pintype "passive"))
      (node (ref "C17") (pin "2") (pinfunction "2_2") (pintype "passive"))
      (node (ref "C18") (pin "2") (pinfunction "2_2") (pintype "passive"))
      (node (ref "C19") (pin "2") (pinfunction "2_2") (pintype "passive"))
      (node (ref "C2") (pin "2") (pinfunction "2_2") (pintype "passive"))
      (node (ref "C20") (pin "2") (pinfunction "2_2") (pintype "passive"))
      (node (ref "C21") (pin "2") (pinfunction "2_2") (pintype "passive"))
      (node (ref "C22") (pin "2") (pinfunction "2_2") (pintype "passive"))
      (node (ref "C23") (pin "2") (pinfunction "2_2") (pintype "passive"))
      (node (ref "C24") (pin "2") (pinfunction "2_2") (pintype "passive"))
      (node (ref "C25") (pin "2") (pinfunction "2_2") (pintype "passive"))
      (node (ref "C26") (pin "2") (pinfunction "2_2") (pintype "passive"))
      (node (ref "C27") (pin "2") (pinfunction "2_2") (pintype "passive"))
      (node (ref "C3") (pin "2") (pinfunction "2_2") (pintype "passive"))
      (node (ref "C4") (pin "2") (pinfunction "2_2") (pintype "passive"))
      (node (ref "C5") (pin "2") (pinfunction "2_2") (pintype "passive"))
      (node (ref "C6") (pin "2") (pinfunction "2_2") (pintype "passive"))
      (node (ref "C7") (pin "2") (pinfunction "2_2") (pintype "passive"))
      (node (ref "C8") (pin "2") (pinfunction "2_2") (pintype "passive"))
      (node (ref "C9") (pin "2") (pinfunction "2_2") (pintype "passive"))
      (node (ref "C96") (pin "2") (pinfunction "2_2") (pintype "passive"))
      (node (ref "C97") (pin "2") (pinfunction "2_2") (pintype "passive"))
      (node (ref "J1") (pin "14") (pinfunction "14_14") (pintype "passive"))
      (node (ref "J1") (pin "2") (pinfunction "2_2") (pintype "passive"))
      (node (ref "J1") (pin "20") (pinfunction "20_20") (pintype "passive"))
      (node (ref "J1") (pin "26") (pinfunction "26_26") (pintype "passive"))
      (node (ref "J1") (pin "32") (pinfunction "32_32") (pintype "passive"))
      (node (ref "J1") (pin "41") (pinfunction "GND_41") (pintype "power_in"))
      (node (ref "J1") (pin "42") (pinfunction "GND_42") (pintype "power_in"))
      (node (ref "J1") (pin "43") (pinfunction "GND_43") (pintype "power_in"))
      (node (ref "J1") (pin "44") (pinfunction "GND_44") (pintype "power_in"))
      (node (ref "J1") (pin "8") (pinfunction "8_8") (pintype "passive"))
      (node (ref "J2") (pin "11") (pinfunction "TDMS_CLK_SH_11") (pintype "passive"))
      (node (ref "J2") (pin "17") (pinfunction "DDC_CEC_GND_17") (pintype "passive"))
      (node (ref "J2") (pin "2") (pinfunction "TDMS_SHLD2_2") (pintype "passive"))
      (node (ref "J2") (pin "20") (pinfunction "SHIELD_20") (pintype "passive"))
      (node (ref "J2") (pin "21") (pinfunction "SHIELD_21") (pintype "passive"))
      (node (ref "J2") (pin "22") (pinfunction "SHIELD_22") (pintype "passive"))
      (node (ref "J2") (pin "23") (pinfunction "SHIELD_23") (pintype "passive"))
      (node (ref "J2") (pin "5") (pinfunction "TDMS_SHLD1_5") (pintype "passive"))
      (node (ref "J2") (pin "8") (pinfunction "TDMS_SHLD0_8") (pintype "passive"))
      (node (ref "Q6") (pin "5") (pinfunction "S_5") (pintype "passive"))
      (node (ref "R43") (pin "1") (pinfunction "1_1") (pintype "passive"))
      (node (ref "U1") (pin "A7") (pinfunction "VSS_A7") (pintype "power_in"))
      (node (ref "U1") (pin "B2") (pinfunction "VSS_B2") (pintype "power_in"))
      (node (ref "U1") (pin "B3") (pinfunction "VSS_B3") (pintype "power_in"))
      (node (ref "U1") (pin "B4") (pinfunction "VSS_B4") (pintype "power_in"))
      (node (ref "U1") (pin "B5") (pinfunction "VSS_B5") (pintype "power_in"))
      (node (ref "U1") (pin "B6") (pinfunction "VSS_B6") (pintype "power_in"))
      (node (ref "U1") (pin "B8") (pinfunction "VSS_B8") (pintype "power_in"))
      (node (ref "U1") (pin "D4") (pinfunction "VSS_D4") (pintype "power_in"))
      (node (ref "U1") (pin "D5") (pinfunction "VSS_D5") (pintype "power_in"))
      (node (ref "U1") (pin "D6") (pinfunction "VSS_D6") (pintype "power_in"))
      (node (ref "U1") (pin "D7") (pinfunction "VSS_D7") (pintype "power_in"))
      (node (ref "U1") (pin "D9") (pinfunction "VSS_D9") (pintype "power_in"))
      (node (ref "U1") (pin "E4") (pinfunction "VSS_E4") (pintype "power_in"))
      (node (ref "U1") (pin "E5") (pinfunction "VSS_E5") (pintype "power_in"))
      (node (ref "U1") (pin "E6") (pinfunction "VSS_E6") (pintype "power_in"))
      (node (ref "U1") (pin "E7") (pinfunction "VSS_E7") (pintype "power_in"))
      (node (ref "U1") (pin "F4") (pinfunction "VSS_F4") (pintype "power_in"))
      (node (ref "U1") (pin "F5") (pinfunction "VSS_F5") (pintype "power_in"))
      (node (ref "U1") (pin "F6") (pinfunction "VSS_F6") (pintype "power_in"))
      (node (ref "U1") (pin "F7") (pinfunction "VSS_F7") (pintype "power_in"))
      (node (ref "U1") (pin "G2") (pinfunction "VSS_G2") (pintype "power_in"))
      (node (ref "U1") (pin "G4") (pinfunction "VPGM_G4") (pintype "power_in"))
      (node (ref "U1") (pin "G5") (pinfunction "TEST_G5") (pintype "input"))
      (node (ref "U1") (pin "G6") (pinfunction "VSS_G6") (pintype "power_in"))
      (node (ref "U1") (pin "G7") (pinfunction "VSS_G7") (pintype "power_in"))
      (node (ref "U1") (pin "G9") (pinfunction "VSS_G9") (pintype "power_in"))
      (node (ref "U1") (pin "J8") (pinfunction "VSS_J8") (pintype "power_in"))
      (node (ref "U2") (pin "3") (pinfunction "GND_3") (pintype "power_in"))
      (node (ref "U2") (pin "7") (pinfunction "GND_7") (pintype "power_in"))
      (node (ref "U3") (pin "3") (pinfunction "GND_3") (pintype "power_in"))
      (node (ref "U3") (pin "7") (pinfunction "GND_7") (pintype "power_in"))
      (node (ref "U4") (pin "3") (pinfunction "GND_3") (pintype "power_in"))
      (node (ref "U4") (pin "7") (pinfunction "GND_7") (pintype "power_in"))
      (node (ref "Y1") (pin "2") (pinfunction "GND_2") (pintype "power_in"))
    )
    (net (code "39") (name "HDMI_5V") (class "Default")
      (node (ref "C96") (pin "1") (pinfunction "1_1") (pintype "passive"))
      (node (ref "R28") (pin "1") (pinfunction "1_1") (pintype "passive"))
    )
    (net (code "40") (name "I2C2_SCL") (class "Default")
      (node (ref "R2") (pin "1") (pinfunction "1_1") (pintype "passive"))
      (node (ref "U1") (pin "J5") (pinfunction "I2C_SCL_J5") (pintype "input"))
    )
    (net (code "41") (name "I2C2_SDA") (class "Default")
      (node (ref "R3") (pin "1") (pinfunction "1_1") (pintype "passive"))
      (node (ref "U1") (pin "K5") (pinfunction "I2C_SDA_K5") (pintype "input"))
    )
    (net (code "42") (name "Net-(Q6A-D)") (class "Default")
      (node (ref "Q6") (pin "3") (pinfunction "G_3") (pintype "passive"))
      (node (ref "Q6") (pin "6") (pinfunction "D_6") (pintype "passive"))
      (node (ref "R21") (pin "1") (pinfunction "1_1") (pintype "passive"))
    )
    (net (code "43") (name "Net-(U1-REXT)") (class "Default")
      (node (ref "R1") (pin "1") (pinfunction "1_1") (pintype "passive"))
      (node (ref "U1") (pin "A2") (pinfunction "REXT_A2") (pintype "passive"))
    )
    (net (code "44") (name "Net-(Y1-OUT)") (class "Default")
      (node (ref "R6") (pin "2") (pinfunction "2_2") (pintype "passive"))
      (node (ref "Y1") (pin "3") (pinfunction "OUT_3") (pintype "output"))
    )
    (net (code "45") (name "PANEL_EL_ON_1") (class "Default")
      (node (ref "J1") (pin "15") (pinfunction "15_15") (pintype "passive"))
    )
    (net (code "46") (name "PANEL_EL_ON_2") (class "Default")
      (node (ref "J1") (pin "17") (pinfunction "17_17") (pintype "passive"))
    )
    (net (code "47") (name "PANEL_MIPI_ERR_1_8V") (class "Default")
      (node (ref "J1") (pin "27") (pinfunction "27_27") (pintype "passive"))
    )
    (net (code "48") (name "PANEL_RESET") (class "Default")
      (node (ref "J1") (pin "29") (pinfunction "29_29") (pintype "passive"))
    )
    (net (code "49") (name "PANEL_VSYNC_1_8V") (class "Default")
      (node (ref "J1") (pin "13") (pinfunction "13_13") (pintype "passive"))
    )
    (net (code "50") (name "VDDC") (class "Default")
      (node (ref "C10") (pin "1") (pinfunction "1_1") (pintype "passive"))
      (node (ref "C11") (pin "1") (pinfunction "1_1") (pintype "passive"))
      (node (ref "C6") (pin "1") (pinfunction "1_1") (pintype "passive"))
      (node (ref "C7") (pin "1") (pinfunction "1_1") (pintype "passive"))
      (node (ref "C8") (pin "1") (pinfunction "1_1") (pintype "passive"))
      (node (ref "C9") (pin "1") (pinfunction "1_1") (pintype "passive"))
      (node (ref "FB2") (pin "2") (pinfunction "2_2") (pintype "passive"))
      (node (ref "U1") (pin "A3") (pinfunction "VDDC2_A3") (pintype "power_in"))
      (node (ref "U1") (pin "K1") (pinfunction "VDDC1_K1") (pintype "power_in"))
      (node (ref "U1") (pin "K10") (pinfunction "VDDC2_K10") (pintype "power_in"))
    )
    (net (code "51") (name "VDDIO") (class "Default")
      (node (ref "C12") (pin "1") (pinfunction "1_1") (pintype "passive"))
      (node (ref "C13") (pin "1") (pinfunction "1_1") (pintype "passive"))
      (node (ref "C14") (pin "1") (pinfunction "1_1") (pintype "passive"))
      (node (ref "C2") (pin "1") (pinfunction "1_1") (pintype "passive"))
      (node (ref "FB1") (pin "2") (pinfunction "2_2") (pintype "passive"))
      (node (ref "R2") (pin "2") (pinfunction "2_2") (pintype "passive"))
      (node (ref "R3") (pin "2") (pinfunction "2_2") (pintype "passive"))
      (node (ref "U1") (pin "K7") (pinfunction "VDDIO2_K7") (pintype "power_in"))
      (node (ref "Y1") (pin "4") (pinfunction "VDD_4") (pintype "power_in"))
    )
    (net (code "52") (name "VDDMIPI") (class "Default")
      (node (ref "C25") (pin "1") (pinfunction "1_1") (pintype "passive"))
      (node (ref "C26") (pin "1") (pinfunction "1_1") (pintype "passive"))
      (node (ref "C27") (pin "1") (pinfunction "1_1") (pintype "passive"))
      (node (ref "FB4") (pin "2") (pinfunction "2_2") (pintype "passive"))
      (node (ref "U1") (pin "D10") (pinfunction "VDD_MIPI_D10") (pintype "power_in"))
    )
    (net (code "53") (name "VDDPLL") (class "Default")
      (node (ref "C3") (pin "1") (pinfunction "1_1") (pintype "passive"))
      (node (ref "C4") (pin "1") (pinfunction "1_1") (pintype "passive"))
      (node (ref "C5") (pin "1") (pinfunction "1_1") (pintype "passive"))
      (node (ref "FB5") (pin "2") (pinfunction "2_2") (pintype "passive"))
      (node (ref "U1") (pin "A8") (pinfunction "VDD_PLL11_A8") (pintype "power_in"))
    )
    (net (code "54") (name "unconnected-(J1-Pad1)") (class "Default")
      (node (ref "J1") (pin "1") (pinfunction "1_1") (pintype "passive+no_connect"))
    )
    (net (code "55") (name "unconnected-(J1-Pad3)") (class "Default")
      (node (ref "J1") (pin "3") (pinfunction "3_3") (pintype "passive+no_connect"))
    )
    (net (code "56") (name "unconnected-(J1-Pad5)") (class "Default")
      (node (ref "J1") (pin "5") (pinfunction "5_5") (pintype "passive+no_connect"))
    )
    (net (code "57") (name "unconnected-(J1-Pad7)") (class "Default")
      (node (ref "J1") (pin "7") (pinfunction "7_7") (pintype "passive+no_connect"))
    )
    (net (code "58") (name "unconnected-(J1-Pad9)") (class "Default")
      (node (ref "J1") (pin "9") (pinfunction "9_9") (pintype "passive+no_connect"))
    )
    (net (code "59") (name "unconnected-(J1-Pad11)") (class "Default")
      (node (ref "J1") (pin "11") (pinfunction "11_11") (pintype "passive+no_connect"))
    )
    (net (code "60") (name "unconnected-(J1-Pad25)") (class "Default")
      (node (ref "J1") (pin "25") (pinfunction "25_25") (pintype "passive+no_connect"))
    )
    (net (code "61") (name "unconnected-(J1-Pad31)") (class "Default")
      (node (ref "J1") (pin "31") (pinfunction "31_31") (pintype "passive+no_connect"))
    )
    (net (code "62") (name "unconnected-(J1-Pad33)") (class "Default")
      (node (ref "J1") (pin "33") (pinfunction "33_33") (pintype "passive+no_connect"))
    )
    (net (code "63") (name "unconnected-(J1-Pad34)") (class "Default")
      (node (ref "J1") (pin "34") (pinfunction "34_34") (pintype "passive"))
    )
    (net (code "64") (name "unconnected-(J2-CEC-Pad13)") (class "Default")
      (node (ref "J2") (pin "13") (pinfunction "CEC_13") (pintype "passive+no_connect"))
    )
    (net (code "65") (name "unconnected-(J2-RESERVED-Pad14)") (class "Default")
      (node (ref "J2") (pin "14") (pinfunction "RESERVED_14") (pintype "passive+no_connect"))
    )
    (net (code "66") (name "unconnected-(U1-A_OSCK-PadG10)") (class "Default")
      (node (ref "U1") (pin "G10") (pinfunction "A_OSCK_G10") (pintype "passive+no_connect"))
    )
    (net (code "67") (name "unconnected-(U1-A_SCK-PadJ9)") (class "Default")
      (node (ref "U1") (pin "J9") (pinfunction "A_SCK_J9") (pintype "passive+no_connect"))
    )
    (net (code "68") (name "unconnected-(U1-A_SD_0-PadH9)") (class "Default")
      (node (ref "U1") (pin "H9") (pinfunction "A_SD_0_H9") (pintype "passive+no_connect"))
    )
    (net (code "69") (name "unconnected-(U1-A_SD_1-PadJ10)") (class "Default")
      (node (ref "U1") (pin "J10") (pinfunction "A_SD_1_J10") (pintype "passive+no_connect"))
    )
    (net (code "70") (name "unconnected-(U1-A_SD_2-PadK9)") (class "Default")
      (node (ref "U1") (pin "K9") (pinfunction "A_SD_2_K9") (pintype "passive+no_connect"))
    )
    (net (code "71") (name "unconnected-(U1-A_SD_3-PadK8)") (class "Default")
      (node (ref "U1") (pin "K8") (pinfunction "A_SD_3_K8") (pintype "passive+no_connect"))
    )
    (net (code "72") (name "unconnected-(U1-A_WFS-PadH10)") (class "Default")
      (node (ref "U1") (pin "H10") (pinfunction "A_WFS_H10") (pintype "passive+no_connect"))
    )
    (net (code "73") (name "unconnected-(U1-BIASDA-PadA4)") (class "Default")
      (node (ref "U1") (pin "A4") (pinfunction "BIASDA_A4") (pintype "passive+no_connect"))
    )
    (net (code "74") (name "unconnected-(U1-CEC-PadH2)") (class "Default")
      (node (ref "U1") (pin "H2") (pinfunction "CEC_H2") (pintype "output+no_connect"))
    )
    (net (code "75") (name "unconnected-(U1-DAOUT-PadA5)") (class "Default")
      (node (ref "U1") (pin "A5") (pinfunction "DAOUT_A5") (pintype "passive+no_connect"))
    )
    (net (code "76") (name "unconnected-(U1-IR-PadJ6)") (class "Default")
      (node (ref "U1") (pin "J6") (pinfunction "IR_J6") (pintype "input+no_connect"))
    )
    (net (code "77") (name "unconnected-(U1-PCKIN-PadB7)") (class "Default")
      (node (ref "U1") (pin "B7") (pinfunction "PCKIN_B7") (pintype "passive+no_connect"))
    )
    (net (code "78") (name "unconnected-(U1-PFIL-PadA6)") (class "Default")
      (node (ref "U1") (pin "A6") (pinfunction "PFIL_A6") (pintype "passive+no_connect"))
    )
  )
)
